# 20200614.net
KiCad netlist of a schematic drawn in Altium Designer
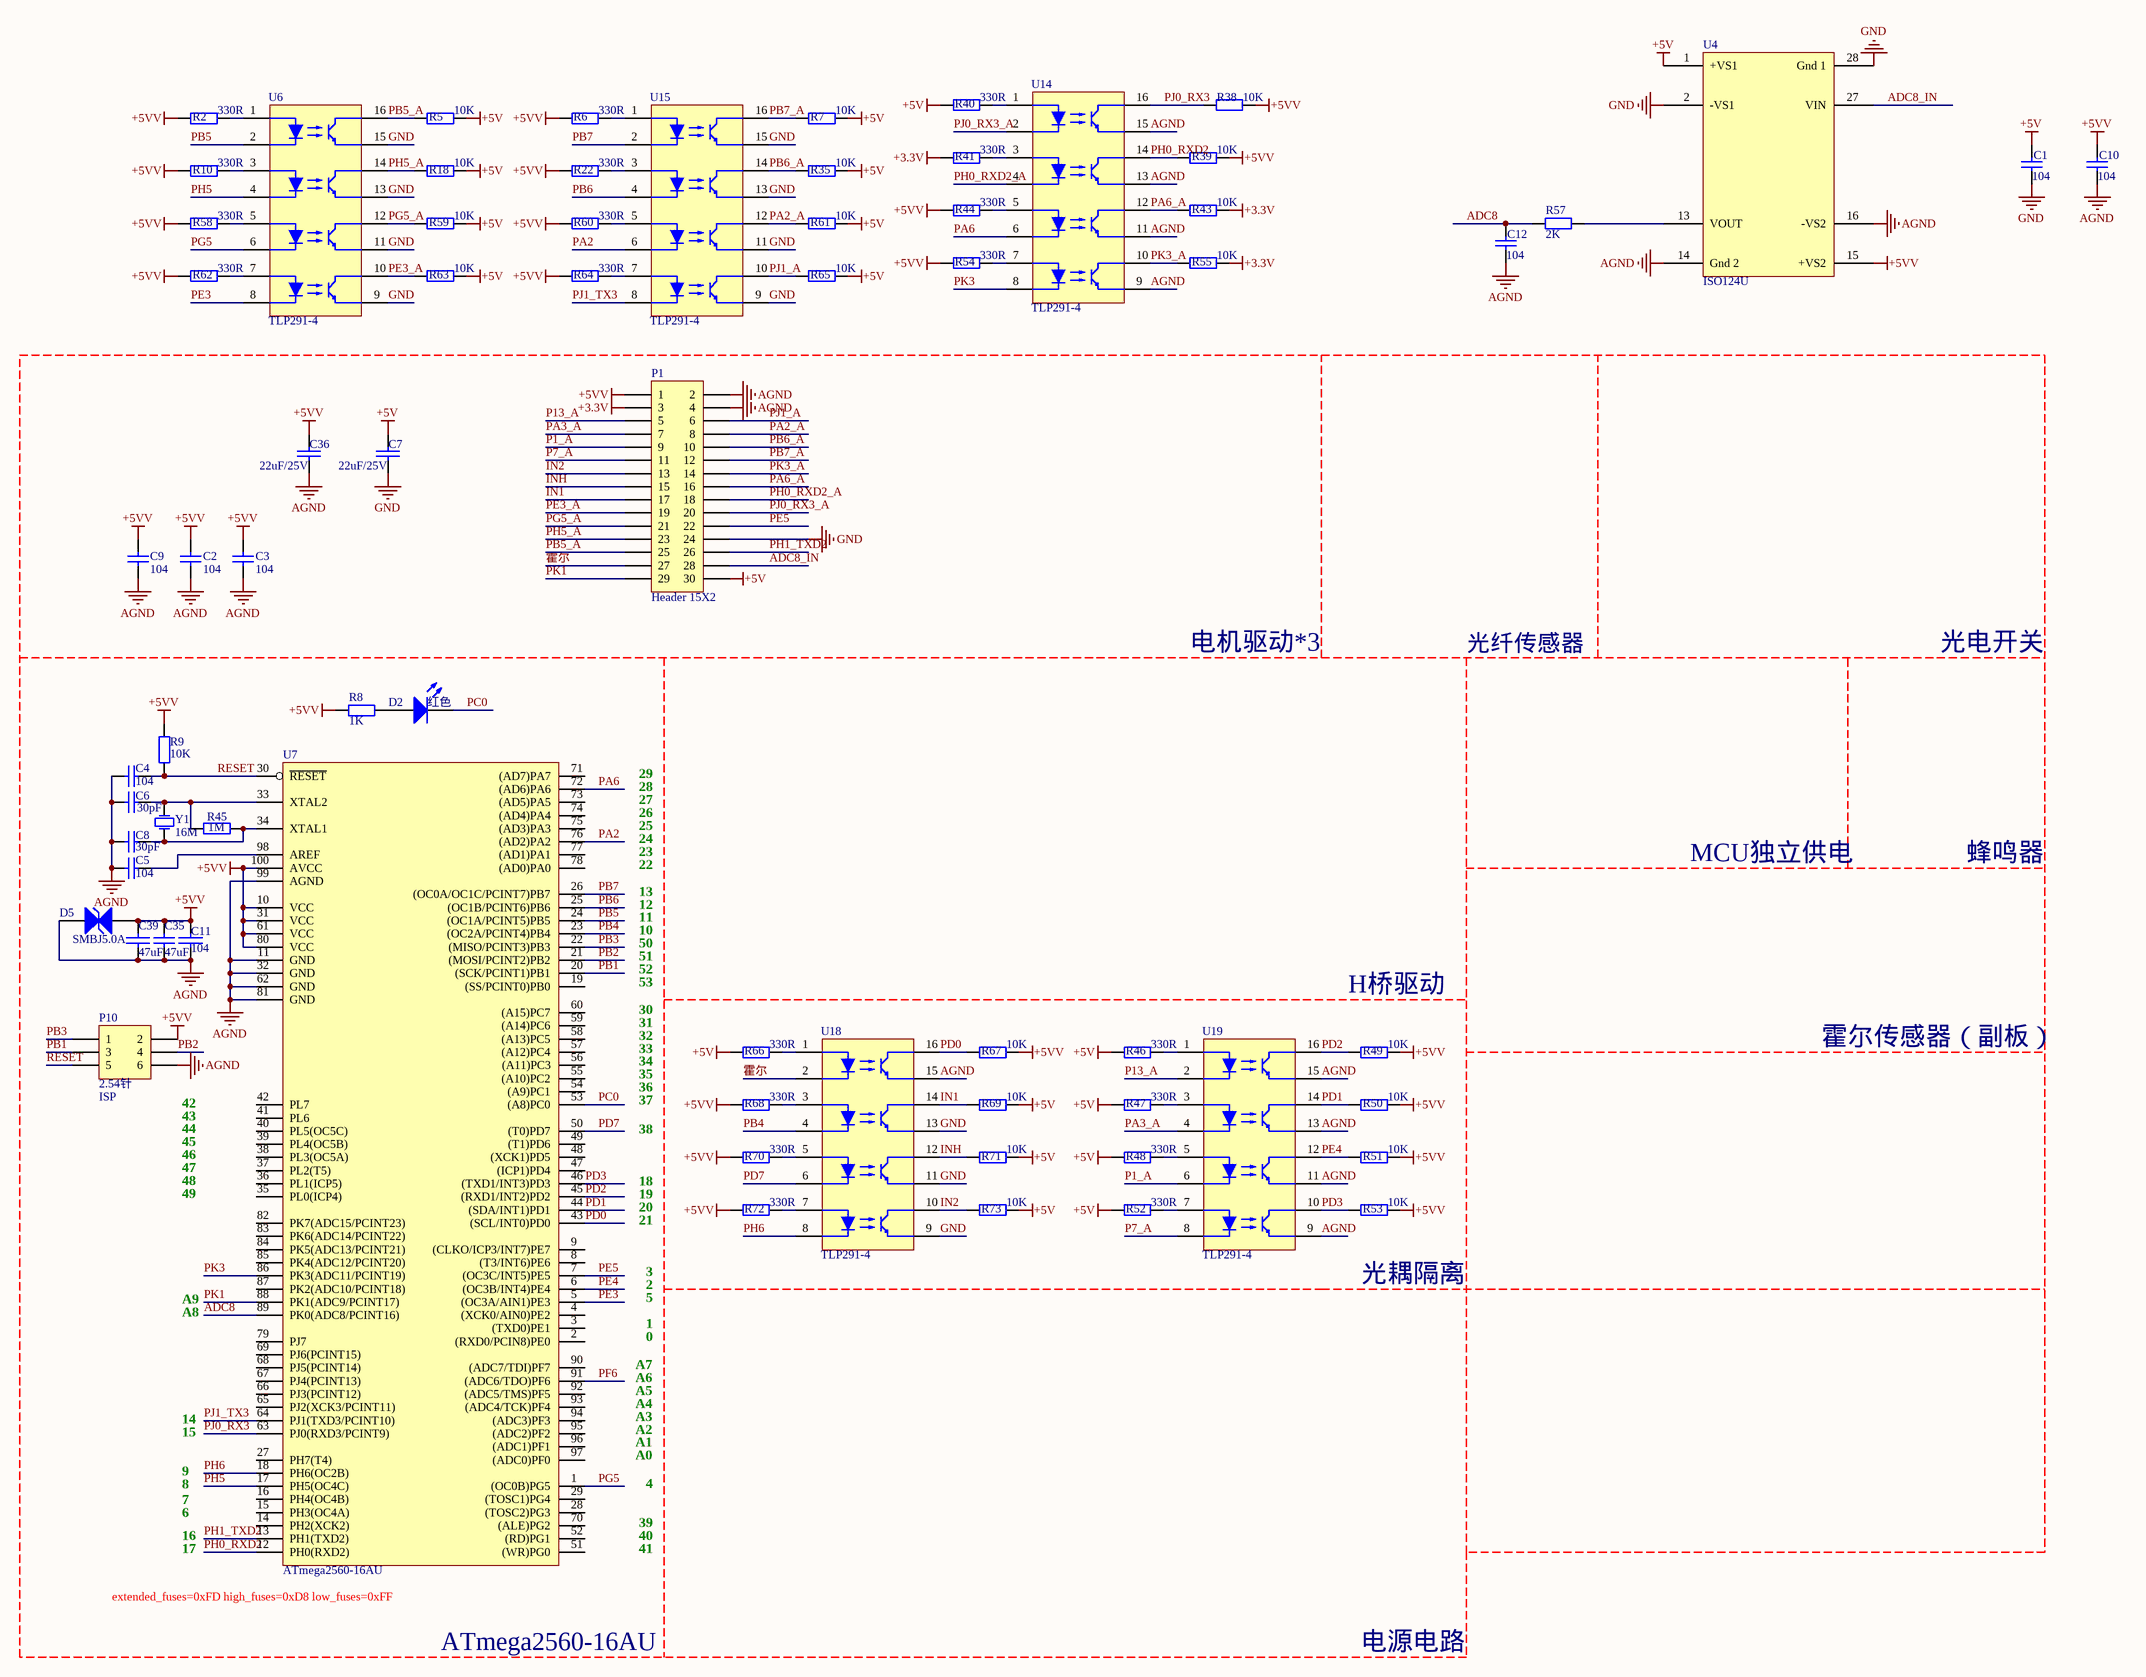
[diagram p0: 剥皮器20200614.SCHDOC]

(export (version "E")
  (design (tool "Eeschema 10.0.6"))
  (components
    (comp (ref "C1")
      (value "104")
      (footprint "0805-C")
      (description "Capacitor")
      (fields (field (name "PUBLISHER") "Altium Limited"))
      (libsource (lib "Miscellaneous Devices") (part "Cap"))
    )
    (comp (ref "C2")
      (value "104")
      (footprint "0805-C")
      (description "Capacitor")
      (fields (field (name "PUBLISHER") "Altium Limited"))
      (libsource (lib "Miscellaneous Devices") (part "Cap"))
    )
    (comp (ref "C3")
      (value "104")
      (footprint "0805-C")
      (description "Capacitor")
      (fields (field (name "PUBLISHER") "Altium Limited"))
      (libsource (lib "Miscellaneous Devices") (part "Cap"))
    )
    (comp (ref "C4")
      (value "104")
      (footprint "0805-C")
      (description "Capacitor")
      (fields (field (name "PUBLISHER") "Altium Limited"))
      (libsource (lib "Miscellaneous Devices") (part "Cap"))
    )
    (comp (ref "C5")
      (value "104")
      (footprint "0805-C")
      (description "Capacitor")
      (fields (field (name "PUBLISHER") "Altium Limited"))
      (libsource (lib "Miscellaneous Devices") (part "Cap"))
    )
    (comp (ref "C6")
      (value "30pF")
      (footprint "0805-C")
      (description "Capacitor")
      (fields (field (name "PUBLISHER") "Altium Limited"))
      (libsource (lib "Miscellaneous Devices") (part "Cap"))
    )
    (comp (ref "C7")
      (value "22uF/25V")
      (footprint "1206C")
      (description "Capacitor")
      (libsource (lib "*") (part "CAP"))
    )
    (comp (ref "C8")
      (value "30pF")
      (footprint "0805-C")
      (description "Capacitor")
      (fields (field (name "PUBLISHER") "Altium Limited"))
      (libsource (lib "Miscellaneous Devices") (part "Cap"))
    )
    (comp (ref "C9")
      (value "104")
      (footprint "0805-C")
      (description "Capacitor")
      (fields (field (name "PUBLISHER") "Altium Limited"))
      (libsource (lib "Miscellaneous Devices") (part "Cap"))
    )
    (comp (ref "C10")
      (value "104")
      (footprint "0805-C")
      (description "Capacitor")
      (fields (field (name "PUBLISHER") "Altium Limited"))
      (libsource (lib "Miscellaneous Devices") (part "Cap"))
    )
    (comp (ref "C11")
      (value "104")
      (footprint "0805-C")
      (description "Capacitor")
      (libsource (lib "*") (part "CAP"))
    )
    (comp (ref "C12")
      (value "104")
      (footprint "0805-C")
      (description "Capacitor")
      (fields (field (name "PUBLISHER") "Altium Limited"))
      (libsource (lib "Miscellaneous Devices") (part "Cap"))
    )
    (comp (ref "C35")
      (value "47uF")
      (footprint "0805-C")
      (description "Capacitor")
      (fields (field (name "PUBLISHER") "Altium Limited"))
      (libsource (lib "Miscellaneous Devices") (part "Cap"))
    )
    (comp (ref "C36")
      (value "22uF/25V")
      (footprint "1206C")
      (description "Capacitor")
      (libsource (lib "*") (part "CAP"))
    )
    (comp (ref "C39")
      (value "47uF")
      (footprint "0805-C")
      (description "Capacitor")
      (libsource (lib "*") (part "CAP"))
    )
    (comp (ref "D2")
      (value "红色")
      (footprint "0805-LED")
      (description "Typical INFRARED GaAs LED")
      (fields (field (name "PUBLISHER") "Altium Limited"))
      (libsource (lib "Miscellaneous Devices") (part "LED0"))
    )
    (comp (ref "D5")
      (value "SMBJ5.0A")
      (footprint "LC-SMB(DO-214AA)_S2")
      (description "TVS")
      (libsource (lib "JW专用元件库") (part "TVS"))
    )
    (comp (ref "P1")
      (value "Header 15X2")
      (footprint "SIP15-1.27")
      (description "Header, 15-Pin, Dual row")
      (fields (field (name "PUBLISHER") "Altium Limited"))
      (libsource (lib "Miscellaneous Connectors") (part "Header 15X2"))
    )
    (comp (ref "P10")
      (value "2.54针")
      (footprint "HDR2X3")
      (description "Header, 3-Pin, Dual row")
      (fields (field (name "ALTIUM_UNNAMED_1") "ISP") (field (name "PUBLISHER") "Altium Limited"))
      (libsource (lib "Miscellaneous Connectors") (part "Header 3X2"))
    )
    (comp (ref "R2")
      (value "330R")
      (footprint "0805-R")
      (description "Resistor")
      (fields (field (name "PUBLISHER") "Altium Limited"))
      (libsource (lib "Miscellaneous Devices") (part "Res2"))
    )
    (comp (ref "R5")
      (value "10K")
      (footprint "0805-R")
      (description "Resistor")
      (fields (field (name "PUBLISHER") "Altium Limited"))
      (libsource (lib "Miscellaneous Devices") (part "Res2"))
    )
    (comp (ref "R6")
      (value "330R")
      (footprint "0805-R")
      (description "Resistor")
      (fields (field (name "PUBLISHER") "Altium Limited"))
      (libsource (lib "Miscellaneous Devices") (part "Res2"))
    )
    (comp (ref "R7")
      (value "10K")
      (footprint "0805-R")
      (description "Resistor")
      (fields (field (name "PUBLISHER") "Altium Limited"))
      (libsource (lib "Miscellaneous Devices") (part "Res2"))
    )
    (comp (ref "R8")
      (value "1K")
      (footprint "0805-R")
      (description "Resistor")
      (fields (field (name "PUBLISHER") "Altium Limited"))
      (libsource (lib "Miscellaneous Devices") (part "Res2"))
    )
    (comp (ref "R9")
      (value "10K")
      (footprint "0805-R")
      (description "Resistor")
      (fields (field (name "PUBLISHER") "Altium Limited"))
      (libsource (lib "") (part "Res2_1"))
    )
    (comp (ref "R10")
      (value "330R")
      (footprint "0805-R")
      (description "Resistor")
      (fields (field (name "PUBLISHER") "Altium Limited"))
      (libsource (lib "Miscellaneous Devices") (part "Res2"))
    )
    (comp (ref "R18")
      (value "10K")
      (footprint "0805-R")
      (description "Resistor")
      (fields (field (name "PUBLISHER") "Altium Limited"))
      (libsource (lib "Miscellaneous Devices") (part "Res2"))
    )
    (comp (ref "R22")
      (value "330R")
      (footprint "0805-R")
      (description "Resistor")
      (fields (field (name "PUBLISHER") "Altium Limited"))
      (libsource (lib "Miscellaneous Devices") (part "Res2"))
    )
    (comp (ref "R35")
      (value "10K")
      (footprint "0805-R")
      (description "Resistor")
      (fields (field (name "PUBLISHER") "Altium Limited"))
      (libsource (lib "Miscellaneous Devices") (part "Res2"))
    )
    (comp (ref "R38")
      (value "10K")
      (footprint "0805-R")
      (description "Resistor")
      (fields (field (name "PUBLISHER") "Altium Limited"))
      (libsource (lib "Miscellaneous Devices") (part "Res2"))
    )
    (comp (ref "R39")
      (value "10K")
      (footprint "0805-R")
      (description "Resistor")
      (fields (field (name "PUBLISHER") "Altium Limited"))
      (libsource (lib "Miscellaneous Devices") (part "Res2"))
    )
    (comp (ref "R40")
      (value "330R")
      (footprint "0805-R")
      (description "Resistor")
      (fields (field (name "PUBLISHER") "Altium Limited"))
      (libsource (lib "Miscellaneous Devices") (part "Res2"))
    )
    (comp (ref "R41")
      (value "330R")
      (footprint "0805-R")
      (description "Resistor")
      (fields (field (name "PUBLISHER") "Altium Limited"))
      (libsource (lib "Miscellaneous Devices") (part "Res2"))
    )
    (comp (ref "R43")
      (value "10K")
      (footprint "0805-R")
      (description "Resistor")
      (fields (field (name "PUBLISHER") "Altium Limited"))
      (libsource (lib "Miscellaneous Devices") (part "Res2"))
    )
    (comp (ref "R44")
      (value "330R")
      (footprint "0805-R")
      (description "Resistor")
      (fields (field (name "PUBLISHER") "Altium Limited"))
      (libsource (lib "Miscellaneous Devices") (part "Res2"))
    )
    (comp (ref "R45")
      (value "1M")
      (footprint "0805-R")
      (description "Resistor")
      (fields (field (name "PUBLISHER") "Altium Limited"))
      (libsource (lib "") (part "Res2_2"))
    )
    (comp (ref "R46")
      (value "330R")
      (footprint "0805-R")
      (description "Resistor")
      (fields (field (name "PUBLISHER") "Altium Limited"))
      (libsource (lib "Miscellaneous Devices") (part "Res2"))
    )
    (comp (ref "R47")
      (value "330R")
      (footprint "0805-R")
      (description "Resistor")
      (fields (field (name "PUBLISHER") "Altium Limited"))
      (libsource (lib "Miscellaneous Devices") (part "Res2"))
    )
    (comp (ref "R48")
      (value "330R")
      (footprint "0805-R")
      (description "Resistor")
      (fields (field (name "PUBLISHER") "Altium Limited"))
      (libsource (lib "Miscellaneous Devices") (part "Res2"))
    )
    (comp (ref "R49")
      (value "10K")
      (footprint "0805-R")
      (description "Resistor")
      (fields (field (name "PUBLISHER") "Altium Limited"))
      (libsource (lib "Miscellaneous Devices") (part "Res2"))
    )
    (comp (ref "R50")
      (value "10K")
      (footprint "0805-R")
      (description "Resistor")
      (fields (field (name "PUBLISHER") "Altium Limited"))
      (libsource (lib "Miscellaneous Devices") (part "Res2"))
    )
    (comp (ref "R51")
      (value "10K")
      (footprint "0805-R")
      (description "Resistor")
      (fields (field (name "PUBLISHER") "Altium Limited"))
      (libsource (lib "Miscellaneous Devices") (part "Res2"))
    )
    (comp (ref "R52")
      (value "330R")
      (footprint "0805-R")
      (description "Resistor")
      (fields (field (name "PUBLISHER") "Altium Limited"))
      (libsource (lib "Miscellaneous Devices") (part "Res2"))
    )
    (comp (ref "R53")
      (value "10K")
      (footprint "0805-R")
      (description "Resistor")
      (fields (field (name "PUBLISHER") "Altium Limited"))
      (libsource (lib "Miscellaneous Devices") (part "Res2"))
    )
    (comp (ref "R54")
      (value "330R")
      (footprint "0805-R")
      (description "Resistor")
      (fields (field (name "PUBLISHER") "Altium Limited"))
      (libsource (lib "Miscellaneous Devices") (part "Res2"))
    )
    (comp (ref "R55")
      (value "10K")
      (footprint "0805-R")
      (description "Resistor")
      (fields (field (name "PUBLISHER") "Altium Limited"))
      (libsource (lib "Miscellaneous Devices") (part "Res2"))
    )
    (comp (ref "R57")
      (value "2K")
      (footprint "0805-R")
      (description "Resistor")
      (fields (field (name "PUBLISHER") "Altium Limited"))
      (libsource (lib "Miscellaneous Devices") (part "Res2"))
    )
    (comp (ref "R58")
      (value "330R")
      (footprint "0805-R")
      (description "Resistor")
      (fields (field (name "PUBLISHER") "Altium Limited"))
      (libsource (lib "Miscellaneous Devices") (part "Res2"))
    )
    (comp (ref "R59")
      (value "10K")
      (footprint "0805-R")
      (description "Resistor")
      (fields (field (name "PUBLISHER") "Altium Limited"))
      (libsource (lib "Miscellaneous Devices") (part "Res2"))
    )
    (comp (ref "R60")
      (value "330R")
      (footprint "0805-R")
      (description "Resistor")
      (fields (field (name "PUBLISHER") "Altium Limited"))
      (libsource (lib "Miscellaneous Devices") (part "Res2"))
    )
    (comp (ref "R61")
      (value "10K")
      (footprint "0805-R")
      (description "Resistor")
      (fields (field (name "PUBLISHER") "Altium Limited"))
      (libsource (lib "Miscellaneous Devices") (part "Res2"))
    )
    (comp (ref "R62")
      (value "330R")
      (footprint "0805-R")
      (description "Resistor")
      (fields (field (name "PUBLISHER") "Altium Limited"))
      (libsource (lib "Miscellaneous Devices") (part "Res2"))
    )
    (comp (ref "R63")
      (value "10K")
      (footprint "0805-R")
      (description "Resistor")
      (fields (field (name "PUBLISHER") "Altium Limited"))
      (libsource (lib "Miscellaneous Devices") (part "Res2"))
    )
    (comp (ref "R64")
      (value "330R")
      (footprint "0805-R")
      (description "Resistor")
      (fields (field (name "PUBLISHER") "Altium Limited"))
      (libsource (lib "Miscellaneous Devices") (part "Res2"))
    )
    (comp (ref "R65")
      (value "10K")
      (footprint "0805-R")
      (description "Resistor")
      (fields (field (name "PUBLISHER") "Altium Limited"))
      (libsource (lib "Miscellaneous Devices") (part "Res2"))
    )
    (comp (ref "R66")
      (value "330R")
      (footprint "0805-R")
      (description "Resistor")
      (fields (field (name "PUBLISHER") "Altium Limited"))
      (libsource (lib "Miscellaneous Devices") (part "Res2"))
    )
    (comp (ref "R67")
      (value "10K")
      (footprint "0805-R")
      (description "Resistor")
      (fields (field (name "PUBLISHER") "Altium Limited"))
      (libsource (lib "Miscellaneous Devices") (part "Res2"))
    )
    (comp (ref "R68")
      (value "330R")
      (footprint "0805-R")
      (description "Resistor")
      (fields (field (name "PUBLISHER") "Altium Limited"))
      (libsource (lib "Miscellaneous Devices") (part "Res2"))
    )
    (comp (ref "R69")
      (value "10K")
      (footprint "0805-R")
      (description "Resistor")
      (fields (field (name "PUBLISHER") "Altium Limited"))
      (libsource (lib "Miscellaneous Devices") (part "Res2"))
    )
    (comp (ref "R70")
      (value "330R")
      (footprint "0805-R")
      (description "Resistor")
      (fields (field (name "PUBLISHER") "Altium Limited"))
      (libsource (lib "Miscellaneous Devices") (part "Res2"))
    )
    (comp (ref "R71")
      (value "10K")
      (footprint "0805-R")
      (description "Resistor")
      (fields (field (name "PUBLISHER") "Altium Limited"))
      (libsource (lib "Miscellaneous Devices") (part "Res2"))
    )
    (comp (ref "R72")
      (value "330R")
      (footprint "0805-R")
      (description "Resistor")
      (fields (field (name "PUBLISHER") "Altium Limited"))
      (libsource (lib "Miscellaneous Devices") (part "Res2"))
    )
    (comp (ref "R73")
      (value "10K")
      (footprint "0805-R")
      (description "Resistor")
      (fields (field (name "PUBLISHER") "Altium Limited"))
      (libsource (lib "Miscellaneous Devices") (part "Res2"))
    )
    (comp (ref "U4")
      (value "ISO124U")
      (footprint "SOIC127P1030X265-8")
      (libsource (lib "Schlib_20110825") (part "ISO124U"))
    )
    (comp (ref "U6")
      (value "TLP291-4")
      (footprint "TLP291-4")
      (description "Photocouplers GaAs Infrared LED & Photo Transistor")
      (libsource (lib "YS_STM32F407_MC") (part "TLP291-4"))
    )
    (comp (ref "U7")
      (value "ATmega2560-16AU")
      (footprint "LC-LQFP-100_14x14x05P")
      (libsource (lib "*") (part "Arduino MEGA 2560"))
    )
    (comp (ref "U14")
      (value "TLP291-4")
      (footprint "TLP291-4")
      (description "Photocouplers GaAs Infrared LED & Photo Transistor")
      (libsource (lib "YS_STM32F407_MC") (part "TLP291-4"))
    )
    (comp (ref "U15")
      (value "TLP291-4")
      (footprint "TLP291-4")
      (description "Photocouplers GaAs Infrared LED & Photo Transistor")
      (libsource (lib "YS_STM32F407_MC") (part "TLP291-4"))
    )
    (comp (ref "U18")
      (value "TLP291-4")
      (footprint "TLP291-4")
      (description "Photocouplers GaAs Infrared LED & Photo Transistor")
      (libsource (lib "YS_STM32F407_MC") (part "TLP291-4"))
    )
    (comp (ref "U19")
      (value "TLP291-4")
      (footprint "TLP291-4")
      (description "Photocouplers GaAs Infrared LED & Photo Transistor")
      (libsource (lib "YS_STM32F407_MC") (part "TLP291-4"))
    )
    (comp (ref "Y1")
      (value "16M")
      (footprint "LC-SMD-5032_2P")
      (description "Crystal Oscillator")
      (fields (field (name "PUBLISHER") "Altium Limited"))
      (libsource (lib "Miscellaneous Devices") (part "XTAL"))
    )
  )
  (nets
    (net (code "1") (name "+3.3V") (class "Default")
      (node (ref "P1") (pin "3") (pinfunction "3_3") (pintype "passive"))
      (node (ref "R41") (pin "2") (pinfunction "2_2") (pintype "passive"))
      (node (ref "R43") (pin "1") (pinfunction "1_1") (pintype "passive"))
      (node (ref "R55") (pin "1") (pinfunction "1_1") (pintype "passive"))
    )
    (net (code "2") (name "+5V") (class "Default")
      (node (ref "C1") (pin "2") (pinfunction "2_2") (pintype "passive"))
      (node (ref "C7") (pin "1") (pinfunction "1_1") (pintype "passive"))
      (node (ref "P1") (pin "30") (pinfunction "30_30") (pintype "passive"))
      (node (ref "R18") (pin "1") (pinfunction "1_1") (pintype "passive"))
      (node (ref "R35") (pin "1") (pinfunction "1_1") (pintype "passive"))
      (node (ref "R40") (pin "2") (pinfunction "2_2") (pintype "passive"))
      (node (ref "R46") (pin "2") (pinfunction "2_2") (pintype "passive"))
      (node (ref "R47") (pin "2") (pinfunction "2_2") (pintype "passive"))
      (node (ref "R48") (pin "2") (pinfunction "2_2") (pintype "passive"))
      (node (ref "R5") (pin "1") (pinfunction "1_1") (pintype "passive"))
      (node (ref "R52") (pin "2") (pinfunction "2_2") (pintype "passive"))
      (node (ref "R59") (pin "1") (pinfunction "1_1") (pintype "passive"))
      (node (ref "R61") (pin "1") (pinfunction "1_1") (pintype "passive"))
      (node (ref "R63") (pin "1") (pinfunction "1_1") (pintype "passive"))
      (node (ref "R65") (pin "1") (pinfunction "1_1") (pintype "passive"))
      (node (ref "R66") (pin "2") (pinfunction "2_2") (pintype "passive"))
      (node (ref "R69") (pin "1") (pinfunction "1_1") (pintype "passive"))
      (node (ref "R7") (pin "1") (pinfunction "1_1") (pintype "passive"))
      (node (ref "R71") (pin "1") (pinfunction "1_1") (pintype "passive"))
      (node (ref "R73") (pin "1") (pinfunction "1_1") (pintype "passive"))
      (node (ref "U4") (pin "1") (pinfunction "+VS1_1") (pintype "passive"))
    )
    (net (code "3") (name "+5VV") (class "Default")
      (node (ref "C10") (pin "2") (pinfunction "2_2") (pintype "passive"))
      (node (ref "C11") (pin "1") (pinfunction "1_1") (pintype "passive"))
      (node (ref "C2") (pin "1") (pinfunction "1_1") (pintype "passive"))
      (node (ref "C3") (pin "1") (pinfunction "1_1") (pintype "passive"))
      (node (ref "C35") (pin "2") (pinfunction "2_2") (pintype "passive"))
      (node (ref "C36") (pin "1") (pinfunction "1_1") (pintype "passive"))
      (node (ref "C39") (pin "2") (pinfunction "2_2") (pintype "passive"))
      (node (ref "C9") (pin "1") (pinfunction "1_1") (pintype "passive"))
      (node (ref "D5") (pin "1") (pinfunction "A_1") (pintype "passive"))
      (node (ref "P1") (pin "1") (pinfunction "1_1") (pintype "passive"))
      (node (ref "P10") (pin "2") (pinfunction "2_2") (pintype "passive"))
      (node (ref "R10") (pin "2") (pinfunction "2_2") (pintype "passive"))
      (node (ref "R2") (pin "2") (pinfunction "2_2") (pintype "passive"))
      (node (ref "R22") (pin "2") (pinfunction "2_2") (pintype "passive"))
      (node (ref "R38") (pin "1") (pinfunction "1_1") (pintype "passive"))
      (node (ref "R39") (pin "1") (pinfunction "1_1") (pintype "passive"))
      (node (ref "R44") (pin "2") (pinfunction "2_2") (pintype "passive"))
      (node (ref "R49") (pin "1") (pinfunction "1_1") (pintype "passive"))
      (node (ref "R50") (pin "1") (pinfunction "1_1") (pintype "passive"))
      (node (ref "R51") (pin "1") (pinfunction "1_1") (pintype "passive"))
      (node (ref "R53") (pin "1") (pinfunction "1_1") (pintype "passive"))
      (node (ref "R54") (pin "2") (pinfunction "2_2") (pintype "passive"))
      (node (ref "R58") (pin "2") (pinfunction "2_2") (pintype "passive"))
      (node (ref "R6") (pin "2") (pinfunction "2_2") (pintype "passive"))
      (node (ref "R60") (pin "2") (pinfunction "2_2") (pintype "passive"))
      (node (ref "R62") (pin "2") (pinfunction "2_2") (pintype "passive"))
      (node (ref "R64") (pin "2") (pinfunction "2_2") (pintype "passive"))
      (node (ref "R67") (pin "1") (pinfunction "1_1") (pintype "passive"))
      (node (ref "R68") (pin "2") (pinfunction "2_2") (pintype "passive"))
      (node (ref "R70") (pin "2") (pinfunction "2_2") (pintype "passive"))
      (node (ref "R72") (pin "2") (pinfunction "2_2") (pintype "passive"))
      (node (ref "R8") (pin "2") (pinfunction "2_2") (pintype "passive"))
      (node (ref "R9") (pin "2") (pinfunction "2_2") (pintype "passive"))
      (node (ref "U4") (pin "15") (pinfunction "+VS2_15") (pintype "passive"))
      (node (ref "U7") (pin "10") (pinfunction "VCC_10") (pintype "passive"))
      (node (ref "U7") (pin "100") (pinfunction "AVCC_100") (pintype "passive"))
      (node (ref "U7") (pin "31") (pinfunction "VCC_31") (pintype "passive"))
      (node (ref "U7") (pin "61") (pinfunction "VCC_61") (pintype "passive"))
      (node (ref "U7") (pin "80") (pinfunction "VCC_80") (pintype "passive"))
    )
    (net (code "4") (name "/ADC8") (class "Default")
      (node (ref "C12") (pin "2") (pinfunction "2_2") (pintype "passive"))
      (node (ref "R57") (pin "2") (pinfunction "2_2") (pintype "passive"))
      (node (ref "U7") (pin "89") (pinfunction "PK0(ADC8/PCINT16)_89") (pintype "passive"))
    )
    (net (code "5") (name "/ADC8_IN") (class "Default")
      (node (ref "P1") (pin "28") (pinfunction "28_28") (pintype "passive"))
      (node (ref "U4") (pin "27") (pinfunction "VIN_27") (pintype "passive"))
    )
    (net (code "6") (name "/IN1") (class "Default")
      (node (ref "P1") (pin "17") (pinfunction "17_17") (pintype "passive"))
      (node (ref "R69") (pin "2") (pinfunction "2_2") (pintype "passive"))
      (node (ref "U18") (pin "14") (pinfunction "Collector2_14") (pintype "passive"))
    )
    (net (code "7") (name "/IN2") (class "Default")
      (node (ref "P1") (pin "13") (pinfunction "13_13") (pintype "passive"))
      (node (ref "R73") (pin "2") (pinfunction "2_2") (pintype "passive"))
      (node (ref "U18") (pin "10") (pinfunction "Collector4_10") (pintype "passive"))
    )
    (net (code "8") (name "/INH") (class "Default")
      (node (ref "P1") (pin "15") (pinfunction "15_15") (pintype "passive"))
      (node (ref "R71") (pin "2") (pinfunction "2_2") (pintype "passive"))
      (node (ref "U18") (pin "12") (pinfunction "Collector3_12") (pintype "passive"))
    )
    (net (code "9") (name "/P1_A") (class "Default")
      (node (ref "P1") (pin "9") (pinfunction "9_9") (pintype "passive"))
      (node (ref "U19") (pin "6") (pinfunction "Cathode3_6") (pintype "passive"))
    )
    (net (code "10") (name "/P7_A") (class "Default")
      (node (ref "P1") (pin "11") (pinfunction "11_11") (pintype "passive"))
      (node (ref "U19") (pin "8") (pinfunction "Cathode4_8") (pintype "passive"))
    )
    (net (code "11") (name "/P13_A") (class "Default")
      (node (ref "P1") (pin "5") (pinfunction "5_5") (pintype "passive"))
      (node (ref "U19") (pin "2") (pinfunction "Cathode1_2") (pintype "passive"))
    )
    (net (code "12") (name "/PA2") (class "Default")
      (node (ref "U15") (pin "6") (pinfunction "Cathode3_6") (pintype "passive"))
      (node (ref "U7") (pin "76") (pinfunction "(AD2)PA2_76") (pintype "passive"))
    )
    (net (code "13") (name "/PA2_A") (class "Default")
      (node (ref "P1") (pin "8") (pinfunction "8_8") (pintype "passive"))
      (node (ref "R61") (pin "2") (pinfunction "2_2") (pintype "passive"))
      (node (ref "U15") (pin "12") (pinfunction "Collector3_12") (pintype "passive"))
    )
    (net (code "14") (name "/PA3_A") (class "Default")
      (node (ref "P1") (pin "7") (pinfunction "7_7") (pintype "passive"))
      (node (ref "U19") (pin "4") (pinfunction "Cathode2_4") (pintype "passive"))
    )
    (net (code "15") (name "/PA6") (class "Default")
      (node (ref "U14") (pin "6") (pinfunction "Cathode3_6") (pintype "passive"))
      (node (ref "U7") (pin "72") (pinfunction "(AD6)PA6_72") (pintype "passive"))
    )
    (net (code "16") (name "/PA6_A") (class "Default")
      (node (ref "P1") (pin "16") (pinfunction "16_16") (pintype "passive"))
      (node (ref "R43") (pin "2") (pinfunction "2_2") (pintype "passive"))
      (node (ref "U14") (pin "12") (pinfunction "Collector3_12") (pintype "passive"))
    )
    (net (code "17") (name "/PB1") (class "Default")
      (node (ref "P10") (pin "3") (pinfunction "3_3") (pintype "passive"))
      (node (ref "U7") (pin "20") (pinfunction "(SCK/PCINT1)PB1_20") (pintype "passive"))
    )
    (net (code "18") (name "/PB2") (class "Default")
      (node (ref "P10") (pin "4") (pinfunction "4_4") (pintype "passive"))
      (node (ref "U7") (pin "21") (pinfunction "(MOSI/PCINT2)PB2_21") (pintype "passive"))
    )
    (net (code "19") (name "/PB3") (class "Default")
      (node (ref "P10") (pin "1") (pinfunction "1_1") (pintype "passive"))
      (node (ref "U7") (pin "22") (pinfunction "(MISO/PCINT3)PB3_22") (pintype "passive"))
    )
    (net (code "20") (name "/PB4") (class "Default")
      (node (ref "U18") (pin "4") (pinfunction "Cathode2_4") (pintype "passive"))
      (node (ref "U7") (pin "23") (pinfunction "(OC2A/PCINT4)PB4_23") (pintype "passive"))
    )
    (net (code "21") (name "/PB5") (class "Default")
      (node (ref "U6") (pin "2") (pinfunction "Cathode1_2") (pintype "passive"))
      (node (ref "U7") (pin "24") (pinfunction "(OC1A/PCINT5)PB5_24") (pintype "passive"))
    )
    (net (code "22") (name "/PB5_A") (class "Default")
      (node (ref "P1") (pin "25") (pinfunction "25_25") (pintype "passive"))
      (node (ref "R5") (pin "2") (pinfunction "2_2") (pintype "passive"))
      (node (ref "U6") (pin "16") (pinfunction "Collector1_16") (pintype "passive"))
    )
    (net (code "23") (name "/PB6") (class "Default")
      (node (ref "U15") (pin "4") (pinfunction "Cathode2_4") (pintype "passive"))
      (node (ref "U7") (pin "25") (pinfunction "(OC1B/PCINT6)PB6_25") (pintype "passive"))
    )
    (net (code "24") (name "/PB6_A") (class "Default")
      (node (ref "P1") (pin "10") (pinfunction "10_10") (pintype "passive"))
      (node (ref "R35") (pin "2") (pinfunction "2_2") (pintype "passive"))
      (node (ref "U15") (pin "14") (pinfunction "Collector2_14") (pintype "passive"))
    )
    (net (code "25") (name "/PB7") (class "Default")
      (node (ref "U15") (pin "2") (pinfunction "Cathode1_2") (pintype "passive"))
      (node (ref "U7") (pin "26") (pinfunction "(OC0A/OC1C/PCINT7)PB7_26") (pintype "passive"))
    )
    (net (code "26") (name "/PB7_A") (class "Default")
      (node (ref "P1") (pin "12") (pinfunction "12_12") (pintype "passive"))
      (node (ref "R7") (pin "2") (pinfunction "2_2") (pintype "passive"))
      (node (ref "U15") (pin "16") (pinfunction "Collector1_16") (pintype "passive"))
    )
    (net (code "27") (name "/PC0") (class "Default")
      (node (ref "D2") (pin "2") (pinfunction "K_2") (pintype "passive"))
      (node (ref "U7") (pin "53") (pinfunction "(A8)PC0_53") (pintype "passive"))
    )
    (net (code "28") (name "/PD0") (class "Default")
      (node (ref "R67") (pin "2") (pinfunction "2_2") (pintype "passive"))
      (node (ref "U18") (pin "16") (pinfunction "Collector1_16") (pintype "passive"))
      (node (ref "U7") (pin "43") (pinfunction "(SCL/INT0)PD0_43") (pintype "passive"))
    )
    (net (code "29") (name "/PD1") (class "Default")
      (node (ref "R50") (pin "2") (pinfunction "2_2") (pintype "passive"))
      (node (ref "U19") (pin "14") (pinfunction "Collector2_14") (pintype "passive"))
      (node (ref "U7") (pin "44") (pinfunction "(SDA/INT1)PD1_44") (pintype "passive"))
    )
    (net (code "30") (name "/PD2") (class "Default")
      (node (ref "R49") (pin "2") (pinfunction "2_2") (pintype "passive"))
      (node (ref "U19") (pin "16") (pinfunction "Collector1_16") (pintype "passive"))
      (node (ref "U7") (pin "45") (pinfunction "(RXD1/INT2)PD2_45") (pintype "passive"))
    )
    (net (code "31") (name "/PD3") (class "Default")
      (node (ref "R53") (pin "2") (pinfunction "2_2") (pintype "passive"))
      (node (ref "U19") (pin "10") (pinfunction "Collector4_10") (pintype "passive"))
      (node (ref "U7") (pin "46") (pinfunction "(TXD1/INT3)PD3_46") (pintype "passive"))
    )
    (net (code "32") (name "/PD7") (class "Default")
      (node (ref "U18") (pin "6") (pinfunction "Cathode3_6") (pintype "passive"))
      (node (ref "U7") (pin "50") (pinfunction "(T0)PD7_50") (pintype "passive"))
    )
    (net (code "33") (name "/PE3") (class "Default")
      (node (ref "U6") (pin "8") (pinfunction "Cathode4_8") (pintype "passive"))
      (node (ref "U7") (pin "5") (pinfunction "(OC3A/AIN1)PE3_5") (pintype "passive"))
    )
    (net (code "34") (name "/PE3_A") (class "Default")
      (node (ref "P1") (pin "19") (pinfunction "19_19") (pintype "passive"))
      (node (ref "R63") (pin "2") (pinfunction "2_2") (pintype "passive"))
      (node (ref "U6") (pin "10") (pinfunction "Collector4_10") (pintype "passive"))
    )
    (net (code "35") (name "/PE4") (class "Default")
      (node (ref "R51") (pin "2") (pinfunction "2_2") (pintype "passive"))
      (node (ref "U19") (pin "12") (pinfunction "Collector3_12") (pintype "passive"))
      (node (ref "U7") (pin "6") (pinfunction "(OC3B/INT4)PE4_6") (pintype "passive"))
    )
    (net (code "36") (name "/PE5") (class "Default")
      (node (ref "P1") (pin "22") (pinfunction "22_22") (pintype "passive"))
      (node (ref "U7") (pin "7") (pinfunction "(OC3C/INT5)PE5_7") (pintype "passive"))
    )
    (net (code "37") (name "/PF6") (class "Default")
      (node (ref "U7") (pin "91") (pinfunction "(ADC6/TDO)PF6_91") (pintype "passive"))
    )
    (net (code "38") (name "/PG5") (class "Default")
      (node (ref "U6") (pin "6") (pinfunction "Cathode3_6") (pintype "passive"))
      (node (ref "U7") (pin "1") (pinfunction "(OC0B)PG5_1") (pintype "passive"))
    )
    (net (code "39") (name "/PG5_A") (class "Default")
      (node (ref "P1") (pin "21") (pinfunction "21_21") (pintype "passive"))
      (node (ref "R59") (pin "2") (pinfunction "2_2") (pintype "passive"))
      (node (ref "U6") (pin "12") (pinfunction "Collector3_12") (pintype "passive"))
    )
    (net (code "40") (name "/PH0_RXD2") (class "Default")
      (node (ref "R39") (pin "2") (pinfunction "2_2") (pintype "passive"))
      (node (ref "U14") (pin "14") (pinfunction "Collector2_14") (pintype "passive"))
      (node (ref "U7") (pin "12") (pinfunction "PH0(RXD2)_12") (pintype "passive"))
    )
    (net (code "41") (name "/PH0_RXD2_A") (class "Default")
      (node (ref "P1") (pin "18") (pinfunction "18_18") (pintype "passive"))
      (node (ref "U14") (pin "4") (pinfunction "Cathode2_4") (pintype "passive"))
    )
    (net (code "42") (name "/PH1_TXD2") (class "Default")
      (node (ref "P1") (pin "26") (pinfunction "26_26") (pintype "passive"))
      (node (ref "U7") (pin "13") (pinfunction "PH1(TXD2)_13") (pintype "passive"))
    )
    (net (code "43") (name "/PH5") (class "Default")
      (node (ref "U6") (pin "4") (pinfunction "Cathode2_4") (pintype "passive"))
      (node (ref "U7") (pin "17") (pinfunction "PH5(OC4C)_17") (pintype "passive"))
    )
    (net (code "44") (name "/PH5_A") (class "Default")
      (node (ref "P1") (pin "23") (pinfunction "23_23") (pintype "passive"))
      (node (ref "R18") (pin "2") (pinfunction "2_2") (pintype "passive"))
      (node (ref "U6") (pin "14") (pinfunction "Collector2_14") (pintype "passive"))
    )
    (net (code "45") (name "/PH6") (class "Default")
      (node (ref "U18") (pin "8") (pinfunction "Cathode4_8") (pintype "passive"))
      (node (ref "U7") (pin "18") (pinfunction "PH6(OC2B)_18") (pintype "passive"))
    )
    (net (code "46") (name "/PJ0_RX3") (class "Default")
      (node (ref "R38") (pin "2") (pinfunction "2_2") (pintype "passive"))
      (node (ref "U14") (pin "16") (pinfunction "Collector1_16") (pintype "passive"))
      (node (ref "U7") (pin "63") (pinfunction "PJ0(RXD3/PCINT9)_63") (pintype "passive"))
    )
    (net (code "47") (name "/PJ0_RX3_A") (class "Default")
      (node (ref "P1") (pin "20") (pinfunction "20_20") (pintype "passive"))
      (node (ref "U14") (pin "2") (pinfunction "Cathode1_2") (pintype "passive"))
    )
    (net (code "48") (name "/PJ1_A") (class "Default")
      (node (ref "P1") (pin "6") (pinfunction "6_6") (pintype "passive"))
      (node (ref "R65") (pin "2") (pinfunction "2_2") (pintype "passive"))
      (node (ref "U15") (pin "10") (pinfunction "Collector4_10") (pintype "passive"))
    )
    (net (code "49") (name "/PJ1_TX3") (class "Default")
      (node (ref "U15") (pin "8") (pinfunction "Cathode4_8") (pintype "passive"))
      (node (ref "U7") (pin "64") (pinfunction "PJ1(TXD3/PCINT10)_64") (pintype "passive"))
    )
    (net (code "50") (name "/PK1") (class "Default")
      (node (ref "P1") (pin "29") (pinfunction "29_29") (pintype "passive"))
      (node (ref "U7") (pin "88") (pinfunction "PK1(ADC9/PCINT17)_88") (pintype "passive"))
    )
    (net (code "51") (name "/PK3") (class "Default")
      (node (ref "U14") (pin "8") (pinfunction "Cathode4_8") (pintype "passive"))
      (node (ref "U7") (pin "86") (pinfunction "PK3(ADC11/PCINT19)_86") (pintype "passive"))
    )
    (net (code "52") (name "/PK3_A") (class "Default")
      (node (ref "P1") (pin "14") (pinfunction "14_14") (pintype "passive"))
      (node (ref "R55") (pin "2") (pinfunction "2_2") (pintype "passive"))
      (node (ref "U14") (pin "10") (pinfunction "Collector4_10") (pintype "passive"))
    )
    (net (code "53") (name "/RESET") (class "Default")
      (node (ref "C4") (pin "1") (pinfunction "1_1") (pintype "passive"))
      (node (ref "P10") (pin "5") (pinfunction "5_5") (pintype "passive"))
      (node (ref "R9") (pin "1") (pinfunction "1_1") (pintype "passive"))
      (node (ref "U7") (pin "30") (pinfunction "~{RESET}_30") (pintype "passive"))
    )
    (net (code "54") (name "/霍尔") (class "Default")
      (node (ref "P1") (pin "27") (pinfunction "27_27") (pintype "passive"))
      (node (ref "U18") (pin "2") (pinfunction "Cathode1_2") (pintype "passive"))
    )
    (net (code "55") (name "AGND") (class "Default")
      (node (ref "C10") (pin "1") (pinfunction "1_1") (pintype "passive"))
      (node (ref "C11") (pin "2") (pinfunction "2_2") (pintype "passive"))
      (node (ref "C12") (pin "1") (pinfunction "1_1") (pintype "passive"))
      (node (ref "C2") (pin "2") (pinfunction "2_2") (pintype "passive"))
      (node (ref "C3") (pin "2") (pinfunction "2_2") (pintype "passive"))
      (node (ref "C35") (pin "1") (pinfunction "1_1") (pintype "passive"))
      (node (ref "C36") (pin "2") (pinfunction "2_2") (pintype "passive"))
      (node (ref "C39") (pin "1") (pinfunction "1_1") (pintype "passive"))
      (node (ref "C4") (pin "2") (pinfunction "2_2") (pintype "passive"))
      (node (ref "C5") (pin "2") (pinfunction "2_2") (pintype "passive"))
      (node (ref "C6") (pin "2") (pinfunction "2_2") (pintype "passive"))
      (node (ref "C8") (pin "2") (pinfunction "2_2") (pintype "passive"))
      (node (ref "C9") (pin "2") (pinfunction "2_2") (pintype "passive"))
      (node (ref "D5") (pin "2") (pinfunction "K_2") (pintype "passive"))
      (node (ref "P1") (pin "2") (pinfunction "2_2") (pintype "passive"))
      (node (ref "P1") (pin "4") (pinfunction "4_4") (pintype "passive"))
      (node (ref "P10") (pin "6") (pinfunction "6_6") (pintype "passive"))
      (node (ref "U14") (pin "11") (pinfunction "Emitter3_11") (pintype "passive"))
      (node (ref "U14") (pin "13") (pinfunction "Emitter2_13") (pintype "passive"))
      (node (ref "U14") (pin "15") (pinfunction "Emitter1_15") (pintype "passive"))
      (node (ref "U14") (pin "9") (pinfunction "Emitter4_9") (pintype "passive"))
      (node (ref "U18") (pin "15") (pinfunction "Emitter1_15") (pintype "passive"))
      (node (ref "U19") (pin "11") (pinfunction "Emitter3_11") (pintype "passive"))
      (node (ref "U19") (pin "13") (pinfunction "Emitter2_13") (pintype "passive"))
      (node (ref "U19") (pin "15") (pinfunction "Emitter1_15") (pintype "passive"))
      (node (ref "U19") (pin "9") (pinfunction "Emitter4_9") (pintype "passive"))
      (node (ref "U4") (pin "14") (pinfunction "Gnd_2_14") (pintype "passive"))
      (node (ref "U4") (pin "16") (pinfunction "-VS2_16") (pintype "passive"))
      (node (ref "U7") (pin "11") (pinfunction "GND_11") (pintype "passive"))
      (node (ref "U7") (pin "32") (pinfunction "GND_32") (pintype "passive"))
      (node (ref "U7") (pin "62") (pinfunction "GND_62") (pintype "passive"))
      (node (ref "U7") (pin "81") (pinfunction "GND_81") (pintype "passive"))
      (node (ref "U7") (pin "99") (pinfunction "AGND_99") (pintype "passive"))
    )
    (net (code "56") (name "GND") (class "Default")
      (node (ref "C1") (pin "1") (pinfunction "1_1") (pintype "passive"))
      (node (ref "C7") (pin "2") (pinfunction "2_2") (pintype "passive"))
      (node (ref "P1") (pin "24") (pinfunction "24_24") (pintype "passive"))
      (node (ref "U15") (pin "11") (pinfunction "Emitter3_11") (pintype "passive"))
      (node (ref "U15") (pin "13") (pinfunction "Emitter2_13") (pintype "passive"))
      (node (ref "U15") (pin "15") (pinfunction "Emitter1_15") (pintype "passive"))
      (node (ref "U15") (pin "9") (pinfunction "Emitter4_9") (pintype "passive"))
      (node (ref "U18") (pin "11") (pinfunction "Emitter3_11") (pintype "passive"))
      (node (ref "U18") (pin "13") (pinfunction "Emitter2_13") (pintype "passive"))
      (node (ref "U18") (pin "9") (pinfunction "Emitter4_9") (pintype "passive"))
      (node (ref "U4") (pin "2") (pinfunction "-VS1_2") (pintype "passive"))
      (node (ref "U4") (pin "28") (pinfunction "Gnd_1_28") (pintype "passive"))
      (node (ref "U6") (pin "11") (pinfunction "Emitter3_11") (pintype "passive"))
      (node (ref "U6") (pin "13") (pinfunction "Emitter2_13") (pintype "passive"))
      (node (ref "U6") (pin "15") (pinfunction "Emitter1_15") (pintype "passive"))
      (node (ref "U6") (pin "9") (pinfunction "Emitter4_9") (pintype "passive"))
    )
    (net (code "57") (name "Net-(D2-A)") (class "Default")
      (node (ref "D2") (pin "1") (pinfunction "A_1") (pintype "passive"))
      (node (ref "R8") (pin "1") (pinfunction "1_1") (pintype "passive"))
    )
    (net (code "58") (name "Net-(U4-VOUT)") (class "Default")
      (node (ref "R57") (pin "1") (pinfunction "1_1") (pintype "passive"))
      (node (ref "U4") (pin "13") (pinfunction "VOUT_13") (pintype "passive"))
    )
    (net (code "59") (name "Net-(U6-Anode1)") (class "Default")
      (node (ref "R2") (pin "1") (pinfunction "1_1") (pintype "passive"))
      (node (ref "U6") (pin "1") (pinfunction "Anode1_1") (pintype "passive"))
    )
    (net (code "60") (name "Net-(U6-Anode2)") (class "Default")
      (node (ref "R10") (pin "1") (pinfunction "1_1") (pintype "passive"))
      (node (ref "U6") (pin "3") (pinfunction "Anode2_3") (pintype "passive"))
    )
    (net (code "61") (name "Net-(U6-Anode3)") (class "Default")
      (node (ref "R58") (pin "1") (pinfunction "1_1") (pintype "passive"))
      (node (ref "U6") (pin "5") (pinfunction "Anode3_5") (pintype "passive"))
    )
    (net (code "62") (name "Net-(U6-Anode4)") (class "Default")
      (node (ref "R62") (pin "1") (pinfunction "1_1") (pintype "passive"))
      (node (ref "U6") (pin "7") (pinfunction "Anode4_7") (pintype "passive"))
    )
    (net (code "63") (name "Net-(U7-AREF)") (class "Default")
      (node (ref "C5") (pin "1") (pinfunction "1_1") (pintype "passive"))
      (node (ref "U7") (pin "98") (pinfunction "AREF_98") (pintype "passive"))
    )
    (net (code "64") (name "Net-(U7-XTAL1)") (class "Default")
      (node (ref "C8") (pin "1") (pinfunction "1_1") (pintype "passive"))
      (node (ref "R45") (pin "2") (pinfunction "2_2") (pintype "passive"))
      (node (ref "U7") (pin "34") (pinfunction "XTAL1_34") (pintype "passive"))
      (node (ref "Y1") (pin "2") (pinfunction "OSC2_2") (pintype "passive"))
    )
    (net (code "65") (name "Net-(U7-XTAL2)") (class "Default")
      (node (ref "C6") (pin "1") (pinfunction "1_1") (pintype "passive"))
      (node (ref "R45") (pin "1") (pinfunction "1_1") (pintype "passive"))
      (node (ref "U7") (pin "33") (pinfunction "XTAL2_33") (pintype "passive"))
      (node (ref "Y1") (pin "1") (pinfunction "OSC1_1") (pintype "passive"))
    )
    (net (code "66") (name "Net-(U14-Anode1)") (class "Default")
      (node (ref "R40") (pin "1") (pinfunction "1_1") (pintype "passive"))
      (node (ref "U14") (pin "1") (pinfunction "Anode1_1") (pintype "passive"))
    )
    (net (code "67") (name "Net-(U14-Anode2)") (class "Default")
      (node (ref "R41") (pin "1") (pinfunction "1_1") (pintype "passive"))
      (node (ref "U14") (pin "3") (pinfunction "Anode2_3") (pintype "passive"))
    )
    (net (code "68") (name "Net-(U14-Anode3)") (class "Default")
      (node (ref "R44") (pin "1") (pinfunction "1_1") (pintype "passive"))
      (node (ref "U14") (pin "5") (pinfunction "Anode3_5") (pintype "passive"))
    )
    (net (code "69") (name "Net-(U14-Anode4)") (class "Default")
      (node (ref "R54") (pin "1") (pinfunction "1_1") (pintype "passive"))
      (node (ref "U14") (pin "7") (pinfunction "Anode4_7") (pintype "passive"))
    )
    (net (code "70") (name "Net-(U15-Anode1)") (class "Default")
      (node (ref "R6") (pin "1") (pinfunction "1_1") (pintype "passive"))
      (node (ref "U15") (pin "1") (pinfunction "Anode1_1") (pintype "passive"))
    )
    (net (code "71") (name "Net-(U15-Anode2)") (class "Default")
      (node (ref "R22") (pin "1") (pinfunction "1_1") (pintype "passive"))
      (node (ref "U15") (pin "3") (pinfunction "Anode2_3") (pintype "passive"))
    )
    (net (code "72") (name "Net-(U15-Anode3)") (class "Default")
      (node (ref "R60") (pin "1") (pinfunction "1_1") (pintype "passive"))
      (node (ref "U15") (pin "5") (pinfunction "Anode3_5") (pintype "passive"))
    )
    (net (code "73") (name "Net-(U15-Anode4)") (class "Default")
      (node (ref "R64") (pin "1") (pinfunction "1_1") (pintype "passive"))
      (node (ref "U15") (pin "7") (pinfunction "Anode4_7") (pintype "passive"))
    )
    (net (code "74") (name "Net-(U18-Anode1)") (class "Default")
      (node (ref "R66") (pin "1") (pinfunction "1_1") (pintype "passive"))
      (node (ref "U18") (pin "1") (pinfunction "Anode1_1") (pintype "passive"))
    )
    (net (code "75") (name "Net-(U18-Anode2)") (class "Default")
      (node (ref "R68") (pin "1") (pinfunction "1_1") (pintype "passive"))
      (node (ref "U18") (pin "3") (pinfunction "Anode2_3") (pintype "passive"))
    )
    (net (code "76") (name "Net-(U18-Anode3)") (class "Default")
      (node (ref "R70") (pin "1") (pinfunction "1_1") (pintype "passive"))
      (node (ref "U18") (pin "5") (pinfunction "Anode3_5") (pintype "passive"))
    )
    (net (code "77") (name "Net-(U18-Anode4)") (class "Default")
      (node (ref "R72") (pin "1") (pinfunction "1_1") (pintype "passive"))
      (node (ref "U18") (pin "7") (pinfunction "Anode4_7") (pintype "passive"))
    )
    (net (code "78") (name "Net-(U19-Anode1)") (class "Default")
      (node (ref "R46") (pin "1") (pinfunction "1_1") (pintype "passive"))
      (node (ref "U19") (pin "1") (pinfunction "Anode1_1") (pintype "passive"))
    )
    (net (code "79") (name "Net-(U19-Anode2)") (class "Default")
      (node (ref "R47") (pin "1") (pinfunction "1_1") (pintype "passive"))
      (node (ref "U19") (pin "3") (pinfunction "Anode2_3") (pintype "passive"))
    )
    (net (code "80") (name "Net-(U19-Anode3)") (class "Default")
      (node (ref "R48") (pin "1") (pinfunction "1_1") (pintype "passive"))
      (node (ref "U19") (pin "5") (pinfunction "Anode3_5") (pintype "passive"))
    )
    (net (code "81") (name "Net-(U19-Anode4)") (class "Default")
      (node (ref "R52") (pin "1") (pinfunction "1_1") (pintype "passive"))
      (node (ref "U19") (pin "7") (pinfunction "Anode4_7") (pintype "passive"))
    )
    (net (code "82") (name "unconnected-(U7-(A9)PC1-Pad54)") (class "Default")
      (node (ref "U7") (pin "54") (pinfunction "(A9)PC1_54") (pintype "passive"))
    )
    (net (code "83") (name "unconnected-(U7-(A10)PC2-Pad55)") (class "Default")
      (node (ref "U7") (pin "55") (pinfunction "(A10)PC2_55") (pintype "passive"))
    )
    (net (code "84") (name "unconnected-(U7-(A11)PC3-Pad56)") (class "Default")
      (node (ref "U7") (pin "56") (pinfunction "(A11)PC3_56") (pintype "passive"))
    )
    (net (code "85") (name "unconnected-(U7-(A12)PC4-Pad57)") (class "Default")
      (node (ref "U7") (pin "57") (pinfunction "(A12)PC4_57") (pintype "passive"))
    )
    (net (code "86") (name "unconnected-(U7-(A13)PC5-Pad58)") (class "Default")
      (node (ref "U7") (pin "58") (pinfunction "(A13)PC5_58") (pintype "passive"))
    )
    (net (code "87") (name "unconnected-(U7-(A14)PC6-Pad59)") (class "Default")
      (node (ref "U7") (pin "59") (pinfunction "(A14)PC6_59") (pintype "passive"))
    )
    (net (code "88") (name "unconnected-(U7-(A15)PC7-Pad60)") (class "Default")
      (node (ref "U7") (pin "60") (pinfunction "(A15)PC7_60") (pintype "passive"))
    )
    (net (code "89") (name "unconnected-(U7-(AD0)PA0-Pad78)") (class "Default")
      (node (ref "U7") (pin "78") (pinfunction "(AD0)PA0_78") (pintype "passive"))
    )
    (net (code "90") (name "unconnected-(U7-(AD1)PA1-Pad77)") (class "Default")
      (node (ref "U7") (pin "77") (pinfunction "(AD1)PA1_77") (pintype "passive"))
    )
    (net (code "91") (name "unconnected-(U7-(AD3)PA3-Pad75)") (class "Default")
      (node (ref "U7") (pin "75") (pinfunction "(AD3)PA3_75") (pintype "passive"))
    )
    (net (code "92") (name "unconnected-(U7-(AD4)PA4-Pad74)") (class "Default")
      (node (ref "U7") (pin "74") (pinfunction "(AD4)PA4_74") (pintype "passive"))
    )
    (net (code "93") (name "unconnected-(U7-(AD5)PA5-Pad73)") (class "Default")
      (node (ref "U7") (pin "73") (pinfunction "(AD5)PA5_73") (pintype "passive"))
    )
    (net (code "94") (name "unconnected-(U7-(AD7)PA7-Pad71)") (class "Default")
      (node (ref "U7") (pin "71") (pinfunction "(AD7)PA7_71") (pintype "passive"))
    )
    (net (code "95") (name "unconnected-(U7-(ADC0)PF0-Pad97)") (class "Default")
      (node (ref "U7") (pin "97") (pinfunction "(ADC0)PF0_97") (pintype "passive"))
    )
    (net (code "96") (name "unconnected-(U7-(ADC1)PF1-Pad96)") (class "Default")
      (node (ref "U7") (pin "96") (pinfunction "(ADC1)PF1_96") (pintype "passive"))
    )
    (net (code "97") (name "unconnected-(U7-(ADC2)PF2-Pad95)") (class "Default")
      (node (ref "U7") (pin "95") (pinfunction "(ADC2)PF2_95") (pintype "passive"))
    )
    (net (code "98") (name "unconnected-(U7-(ADC3)PF3-Pad94)") (class "Default")
      (node (ref "U7") (pin "94") (pinfunction "(ADC3)PF3_94") (pintype "passive"))
    )
    (net (code "99") (name "unconnected-(U7-(ADC4{slash}TCK)PF4-Pad93)") (class "Default")
      (node (ref "U7") (pin "93") (pinfunction "(ADC4/TCK)PF4_93") (pintype "passive"))
    )
    (net (code "100") (name "unconnected-(U7-(ADC5{slash}TMS)PF5-Pad92)") (class "Default")
      (node (ref "U7") (pin "92") (pinfunction "(ADC5/TMS)PF5_92") (pintype "passive"))
    )
    (net (code "101") (name "unconnected-(U7-(ADC7{slash}TDI)PF7-Pad90)") (class "Default")
      (node (ref "U7") (pin "90") (pinfunction "(ADC7/TDI)PF7_90") (pintype "passive"))
    )
    (net (code "102") (name "unconnected-(U7-(ALE)PG2-Pad70)") (class "Default")
      (node (ref "U7") (pin "70") (pinfunction "(ALE)PG2_70") (pintype "passive"))
    )
    (net (code "103") (name "unconnected-(U7-(CLKO{slash}ICP3{slash}INT7)PE7-Pad9)") (class "Default")
      (node (ref "U7") (pin "9") (pinfunction "(CLKO/ICP3/INT7)PE7_9") (pintype "passive"))
    )
    (net (code "104") (name "unconnected-(U7-(ICP1)PD4-Pad47)") (class "Default")
      (node (ref "U7") (pin "47") (pinfunction "(ICP1)PD4_47") (pintype "passive"))
    )
    (net (code "105") (name "unconnected-(U7-(RD)PG1-Pad52)") (class "Default")
      (node (ref "U7") (pin "52") (pinfunction "(RD)PG1_52") (pintype "passive"))
    )
    (net (code "106") (name "unconnected-(U7-(RXD0{slash}PCIN8)PE0-Pad2)") (class "Default")
      (node (ref "U7") (pin "2") (pinfunction "(RXD0/PCIN8)PE0_2") (pintype "passive"))
    )
    (net (code "107") (name "unconnected-(U7-(SS{slash}PCINT0)PB0-Pad19)") (class "Default")
      (node (ref "U7") (pin "19") (pinfunction "(SS/PCINT0)PB0_19") (pintype "passive"))
    )
    (net (code "108") (name "unconnected-(U7-(T1)PD6-Pad49)") (class "Default")
      (node (ref "U7") (pin "49") (pinfunction "(T1)PD6_49") (pintype "passive"))
    )
    (net (code "109") (name "unconnected-(U7-(T3{slash}INT6)PE6-Pad8)") (class "Default")
      (node (ref "U7") (pin "8") (pinfunction "(T3/INT6)PE6_8") (pintype "passive"))
    )
    (net (code "110") (name "unconnected-(U7-(TOSC1)PG4-Pad29)") (class "Default")
      (node (ref "U7") (pin "29") (pinfunction "(TOSC1)PG4_29") (pintype "passive"))
    )
    (net (code "111") (name "unconnected-(U7-(TOSC2)PG3-Pad28)") (class "Default")
      (node (ref "U7") (pin "28") (pinfunction "(TOSC2)PG3_28") (pintype "passive"))
    )
    (net (code "112") (name "unconnected-(U7-(TXD0)PE1-Pad3)") (class "Default")
      (node (ref "U7") (pin "3") (pinfunction "(TXD0)PE1_3") (pintype "passive"))
    )
    (net (code "113") (name "unconnected-(U7-(WR)PG0-Pad51)") (class "Default")
      (node (ref "U7") (pin "51") (pinfunction "(WR)PG0_51") (pintype "passive"))
    )
    (net (code "114") (name "unconnected-(U7-(XCK0{slash}AIN0)PE2-Pad4)") (class "Default")
      (node (ref "U7") (pin "4") (pinfunction "(XCK0/AIN0)PE2_4") (pintype "passive"))
    )
    (net (code "115") (name "unconnected-(U7-(XCK1)PD5-Pad48)") (class "Default")
      (node (ref "U7") (pin "48") (pinfunction "(XCK1)PD5_48") (pintype "passive"))
    )
    (net (code "116") (name "unconnected-(U7-PH2(XCK2)-Pad14)") (class "Default")
      (node (ref "U7") (pin "14") (pinfunction "PH2(XCK2)_14") (pintype "passive"))
    )
    (net (code "117") (name "unconnected-(U7-PH3(OC4A)-Pad15)") (class "Default")
      (node (ref "U7") (pin "15") (pinfunction "PH3(OC4A)_15") (pintype "passive"))
    )
    (net (code "118") (name "unconnected-(U7-PH4(OC4B)-Pad16)") (class "Default")
      (node (ref "U7") (pin "16") (pinfunction "PH4(OC4B)_16") (pintype "passive"))
    )
    (net (code "119") (name "unconnected-(U7-PH7(T4)-Pad27)") (class "Default")
      (node (ref "U7") (pin "27") (pinfunction "PH7(T4)_27") (pintype "passive"))
    )
    (net (code "120") (name "unconnected-(U7-PJ2(XCK3{slash}PCINT11)-Pad65)") (class "Default")
      (node (ref "U7") (pin "65") (pinfunction "PJ2(XCK3/PCINT11)_65") (pintype "passive"))
    )
    (net (code "121") (name "unconnected-(U7-PJ3(PCINT12)-Pad66)") (class "Default")
      (node (ref "U7") (pin "66") (pinfunction "PJ3(PCINT12)_66") (pintype "passive"))
    )
    (net (code "122") (name "unconnected-(U7-PJ4(PCINT13)-Pad67)") (class "Default")
      (node (ref "U7") (pin "67") (pinfunction "PJ4(PCINT13)_67") (pintype "passive"))
    )
    (net (code "123") (name "unconnected-(U7-PJ5(PCINT14)-Pad68)") (class "Default")
      (node (ref "U7") (pin "68") (pinfunction "PJ5(PCINT14)_68") (pintype "passive"))
    )
    (net (code "124") (name "unconnected-(U7-PJ6(PCINT15)-Pad69)") (class "Default")
      (node (ref "U7") (pin "69") (pinfunction "PJ6(PCINT15)_69") (pintype "passive"))
    )
    (net (code "125") (name "unconnected-(U7-PJ7-Pad79)") (class "Default")
      (node (ref "U7") (pin "79") (pinfunction "PJ7_79") (pintype "passive"))
    )
    (net (code "126") (name "unconnected-(U7-PK2(ADC10{slash}PCINT18)-Pad87)") (class "Default")
      (node (ref "U7") (pin "87") (pinfunction "PK2(ADC10/PCINT18)_87") (pintype "passive"))
    )
    (net (code "127") (name "unconnected-(U7-PK4(ADC12{slash}PCINT20)-Pad85)") (class "Default")
      (node (ref "U7") (pin "85") (pinfunction "PK4(ADC12/PCINT20)_85") (pintype "passive"))
    )
    (net (code "128") (name "unconnected-(U7-PK5(ADC13{slash}PCINT21)-Pad84)") (class "Default")
      (node (ref "U7") (pin "84") (pinfunction "PK5(ADC13/PCINT21)_84") (pintype "passive"))
    )
    (net (code "129") (name "unconnected-(U7-PK6(ADC14{slash}PCINT22)-Pad83)") (class "Default")
      (node (ref "U7") (pin "83") (pinfunction "PK6(ADC14/PCINT22)_83") (pintype "passive"))
    )
    (net (code "130") (name "unconnected-(U7-PK7(ADC15{slash}PCINT23)-Pad82)") (class "Default")
      (node (ref "U7") (pin "82") (pinfunction "PK7(ADC15/PCINT23)_82") (pintype "passive"))
    )
    (net (code "131") (name "unconnected-(U7-PL0(ICP4)-Pad35)") (class "Default")
      (node (ref "U7") (pin "35") (pinfunction "PL0(ICP4)_35") (pintype "passive"))
    )
    (net (code "132") (name "unconnected-(U7-PL1(ICP5)-Pad36)") (class "Default")
      (node (ref "U7") (pin "36") (pinfunction "PL1(ICP5)_36") (pintype "passive"))
    )
    (net (code "133") (name "unconnected-(U7-PL2(T5)-Pad37)") (class "Default")
      (node (ref "U7") (pin "37") (pinfunction "PL2(T5)_37") (pintype "passive"))
    )
    (net (code "134") (name "unconnected-(U7-PL3(OC5A)-Pad38)") (class "Default")
      (node (ref "U7") (pin "38") (pinfunction "PL3(OC5A)_38") (pintype "passive"))
    )
    (net (code "135") (name "unconnected-(U7-PL4(OC5B)-Pad39)") (class "Default")
      (node (ref "U7") (pin "39") (pinfunction "PL4(OC5B)_39") (pintype "passive"))
    )
    (net (code "136") (name "unconnected-(U7-PL5(OC5C)-Pad40)") (class "Default")
      (node (ref "U7") (pin "40") (pinfunction "PL5(OC5C)_40") (pintype "passive"))
    )
    (net (code "137") (name "unconnected-(U7-PL6-Pad41)") (class "Default")
      (node (ref "U7") (pin "41") (pinfunction "PL6_41") (pintype "passive"))
    )
    (net (code "138") (name "unconnected-(U7-PL7-Pad42)") (class "Default")
      (node (ref "U7") (pin "42") (pinfunction "PL7_42") (pintype "passive"))
    )
  )
)
